# Module2.net
KiCad netlist of a schematic drawn in EAGLE
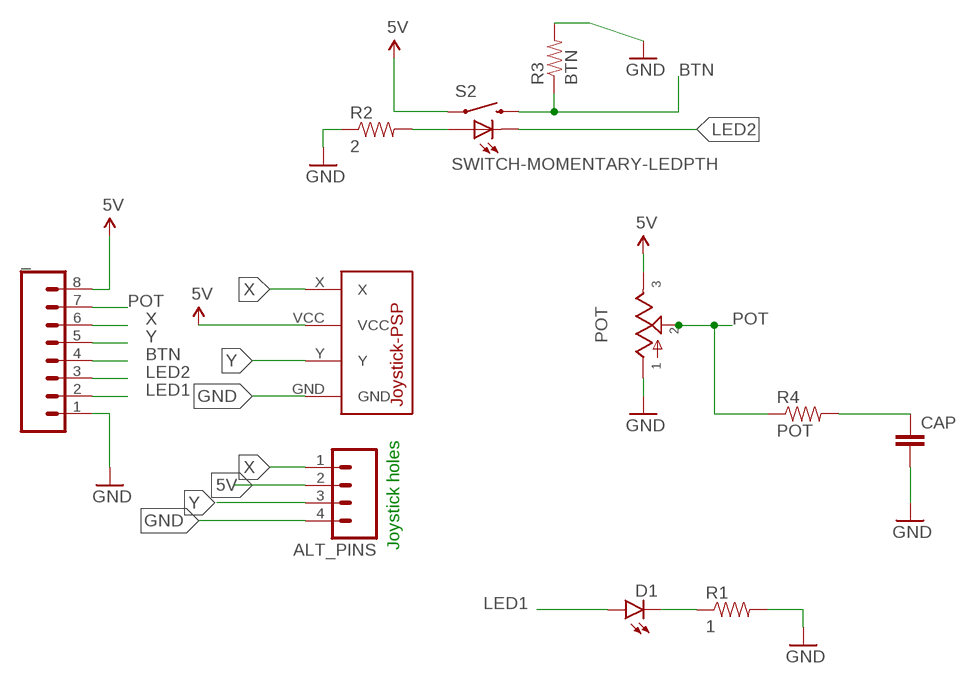
[diagram p0: schematic, sheet 1]

(export (version "E")
  (design (tool "Eeschema 10.0.6"))
  (components
    (comp (ref "ALT_PINS")
      (value "M04NO_SILK_ALL_ROUND")
      (footprint "eagle-import:1X04_NO_SILK_ALL_ROUND")
      (libsource (lib "eagle-import") (part "M04NO_SILK_ALL_ROUND"))
    )
    (comp (ref "CAP")
      (value "CAPEZ")
      (footprint "eagle-import:CAP-PTH-SMALLEZ")
      (libsource (lib "eagle-import") (part "CAPEZ"))
    )
    (comp (ref "D1")
      (value "LED3MM")
      (footprint "eagle-import:LED3MM")
      (libsource (lib "eagle-import") (part "LED3MM"))
    )
    (comp (ref "POT")
      (value "POT")
      (footprint "eagle-import:POT")
      (libsource (lib "eagle-import") (part "POT"))
    )
    (comp (ref "R1")
      (value "1")
      (footprint "eagle-import:AXIAL-0.3-KIT")
      (libsource (lib "eagle-import") (part "10KOHM-1/6W-5%(PTH)KIT"))
    )
    (comp (ref "R2")
      (value "2")
      (footprint "eagle-import:AXIAL-0.3-KIT")
      (libsource (lib "eagle-import") (part "10KOHM-1/6W-5%(PTH)KIT"))
    )
    (comp (ref "R3")
      (value "BTN")
      (footprint "eagle-import:AXIAL-0.3-KIT")
      (libsource (lib "eagle-import") (part "10KOHM-1/6W-5%(PTH)KIT"))
    )
    (comp (ref "R4")
      (value "POT")
      (footprint "eagle-import:AXIAL-0.3-KIT")
      (libsource (lib "eagle-import") (part "10KOHM-1/6W-5%(PTH)KIT"))
    )
    (comp (ref "S2")
      (value "SWITCH-MOMENTARY-LEDPTH")
      (footprint "eagle-import:TACTILE-PTH-LED-12MM")
      (libsource (lib "eagle-import") (part "SWITCH-MOMENTARY-LEDPTH"))
    )
    (comp (ref "U$1")
      (value "JOYSTICK-PSP1000")
      (footprint "eagle-import:JOYSTICK-PSP1000")
      (libsource (lib "eagle-import") (part "JOYSTICK-PSP1000"))
    )
    (comp (ref "_")
      (value "M08")
      (footprint "eagle-import:1X08_ROUND")
      (libsource (lib "eagle-import") (part "M08"))
    )
  )
  (nets
    (net (code "1") (name "/BTN") (class "Default")
      (node (ref "R3") (pin "P$1") (pinfunction "1_P$1") (pintype "passive"))
      (node (ref "S2") (pin "2") (pinfunction "2_2") (pintype "passive"))
      (node (ref "_") (pin "4") (pinfunction "4_4") (pintype "passive"))
    )
    (net (code "2") (name "/LED1") (class "Default")
      (node (ref "D1") (pin "A") (pinfunction "A_A") (pintype "passive"))
      (node (ref "_") (pin "2") (pinfunction "2_2") (pintype "passive"))
    )
    (net (code "3") (name "/POT") (class "Default")
      (node (ref "POT") (pin "2") (pinfunction "2_2") (pintype "passive"))
      (node (ref "R4") (pin "P$1") (pinfunction "1_P$1") (pintype "passive"))
      (node (ref "_") (pin "7") (pinfunction "7_7") (pintype "passive"))
    )
    (net (code "4") (name "5V") (class "Default")
      (node (ref "ALT_PINS") (pin "2") (pinfunction "2_2") (pintype "passive"))
      (node (ref "POT") (pin "3") (pinfunction "3_3") (pintype "passive"))
      (node (ref "S2") (pin "4") (pinfunction "1_4") (pintype "passive"))
      (node (ref "U$1") (pin "VCC") (pinfunction "VCC_VCC") (pintype "bidirectional"))
      (node (ref "_") (pin "8") (pinfunction "8_8") (pintype "passive"))
    )
    (net (code "5") (name "GND") (class "Default")
      (node (ref "ALT_PINS") (pin "4") (pinfunction "4_4") (pintype "passive"))
      (node (ref "CAP") (pin "2") (pinfunction "2_2") (pintype "passive"))
      (node (ref "POT") (pin "1") (pinfunction "1_1") (pintype "passive"))
      (node (ref "R1") (pin "P$2") (pinfunction "2_P$2") (pintype "passive"))
      (node (ref "R2") (pin "P$1") (pinfunction "1_P$1") (pintype "passive"))
      (node (ref "R3") (pin "P$2") (pinfunction "2_P$2") (pintype "passive"))
      (node (ref "U$1") (pin "GND") (pinfunction "GND_GND") (pintype "bidirectional"))
      (node (ref "_") (pin "1") (pinfunction "1_1") (pintype "passive"))
    )
    (net (code "6") (name "LED2") (class "Default")
      (node (ref "S2") (pin "C") (pinfunction "C_C") (pintype "passive"))
      (node (ref "_") (pin "3") (pinfunction "3_3") (pintype "passive"))
    )
    (net (code "7") (name "Net-(D1-C)") (class "Default")
      (node (ref "D1") (pin "K") (pinfunction "C_K") (pintype "passive"))
      (node (ref "R1") (pin "P$1") (pinfunction "1_P$1") (pintype "passive"))
    )
    (net (code "8") (name "Net-(R2-2)") (class "Default")
      (node (ref "R2") (pin "P$2") (pinfunction "2_P$2") (pintype "passive"))
      (node (ref "S2") (pin "A") (pinfunction "A_A") (pintype "passive"))
    )
    (net (code "9") (name "Net-(R4-2)") (class "Default")
      (node (ref "CAP") (pin "1") (pinfunction "1_1") (pintype "passive"))
      (node (ref "R4") (pin "P$2") (pinfunction "2_P$2") (pintype "passive"))
    )
    (net (code "10") (name "X") (class "Default")
      (node (ref "ALT_PINS") (pin "1") (pinfunction "1_1") (pintype "passive"))
      (node (ref "U$1") (pin "X") (pinfunction "X_X") (pintype "bidirectional"))
      (node (ref "_") (pin "6") (pinfunction "6_6") (pintype "passive"))
    )
    (net (code "11") (name "Y") (class "Default")
      (node (ref "ALT_PINS") (pin "3") (pinfunction "3_3") (pintype "passive"))
      (node (ref "U$1") (pin "Y") (pinfunction "Y_Y") (pintype "bidirectional"))
      (node (ref "_") (pin "5") (pinfunction "5_5") (pintype "passive"))
    )
  )
)
